# Sheet3.net
KiCad netlist of a schematic drawn in Altium Designer
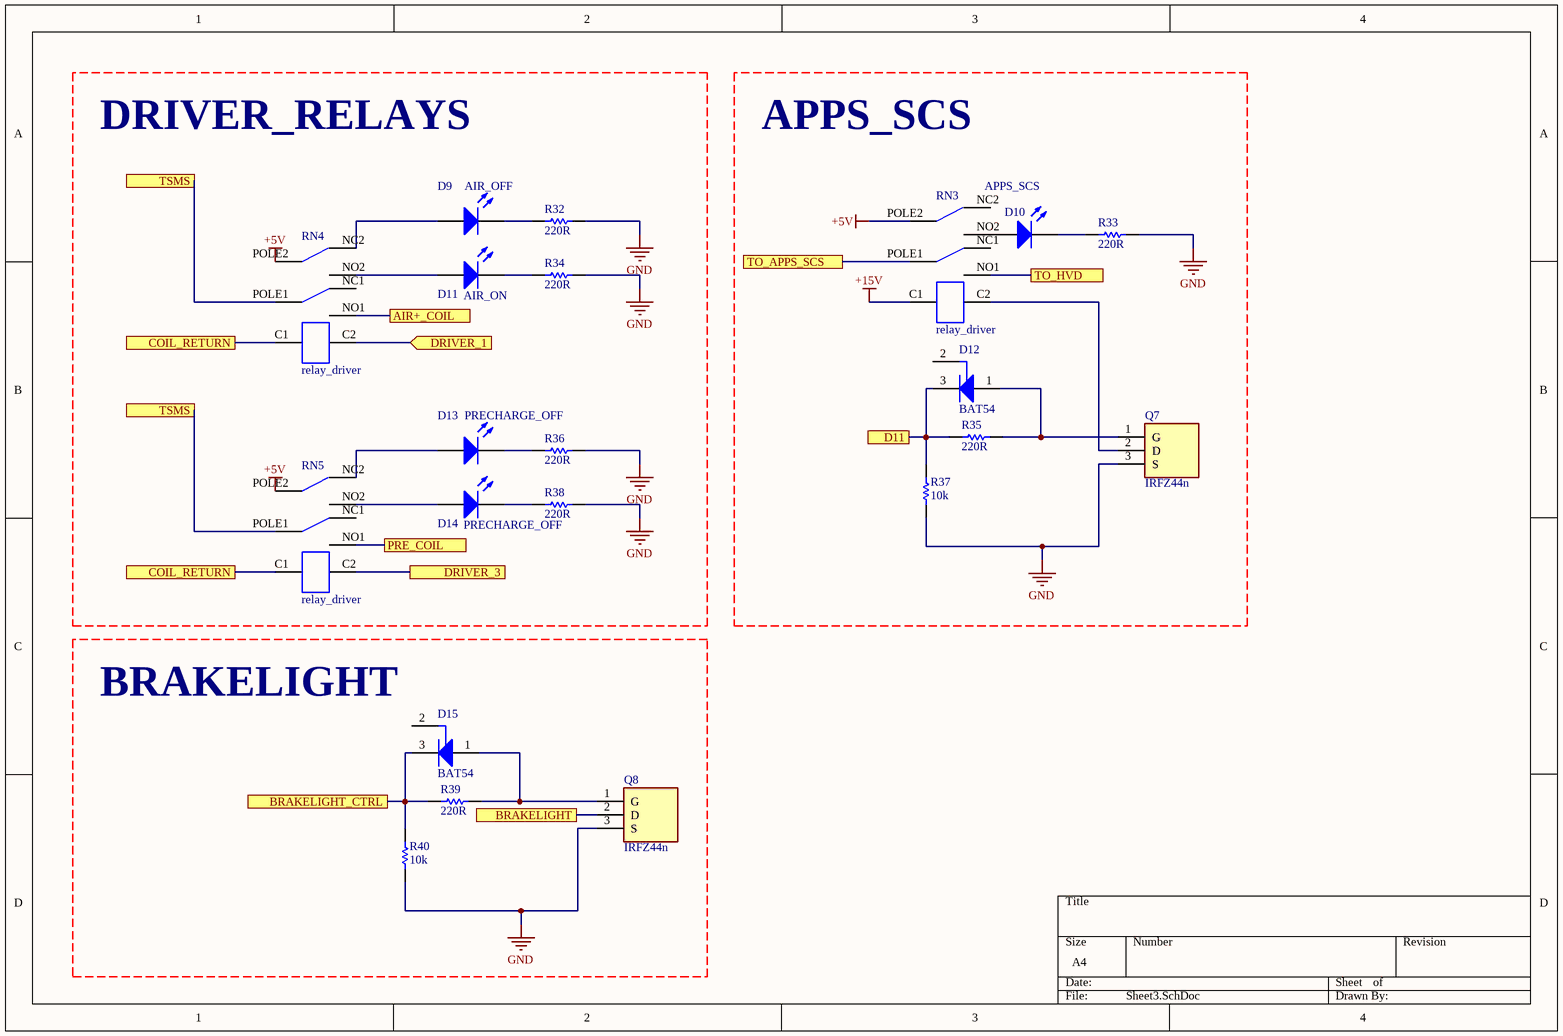
[diagram p0: Sheet3.SchDoc]

(export (version "E")
  (design (tool "Eeschema 10.0.6"))
  (components
    (comp (ref "D9")
      (value "AIR_OFF")
      (footprint "3.2X1.6X1.1")
      (description "Typical RED, GREEN, YELLOW, AMBER GaAs LED")
      (fields (field (name "PUBLISHER") "Altium Limited"))
      (libsource (lib "Miscellaneous Devices") (part "LED2"))
    )
    (comp (ref "D10")
      (value "APPS_SCS")
      (footprint "3.2X1.6X1.1")
      (description "Typical RED, GREEN, YELLOW, AMBER GaAs LED")
      (fields (field (name "PUBLISHER") "Altium Limited"))
      (libsource (lib "Miscellaneous Devices") (part "LED2"))
    )
    (comp (ref "D11")
      (value "AIR_ON")
      (footprint "3.2X1.6X1.1")
      (description "Typical RED, GREEN, YELLOW, AMBER GaAs LED")
      (fields (field (name "PUBLISHER") "Altium Limited"))
      (libsource (lib "Miscellaneous Devices") (part "LED2"))
    )
    (comp (ref "D12")
      (value "BAT54")
      (footprint "INF-SOT23_N")
      (description "Silicon Schottky Diode, SOT23, Reel, Green")
      (fields (field (name "MANUFACTURER") "Infineon"))
      (libsource (lib "Schlib1_TSAL_LV_3.1") (part "CMP-1182-00010-1"))
    )
    (comp (ref "D13")
      (value "PRECHARGE_OFF")
      (footprint "3.2X1.6X1.1")
      (description "Typical RED, GREEN, YELLOW, AMBER GaAs LED")
      (fields (field (name "PUBLISHER") "Altium Limited"))
      (libsource (lib "Miscellaneous Devices") (part "LED2"))
    )
    (comp (ref "D14")
      (value "PRECHARGE_OFF")
      (footprint "3.2X1.6X1.1")
      (description "Typical RED, GREEN, YELLOW, AMBER GaAs LED")
      (fields (field (name "PUBLISHER") "Altium Limited"))
      (libsource (lib "Miscellaneous Devices") (part "LED2"))
    )
    (comp (ref "D15")
      (value "BAT54")
      (footprint "INF-SOT23_N")
      (description "Silicon Schottky Diode, SOT23, Reel, Green")
      (fields (field (name "MANUFACTURER") "Infineon"))
      (libsource (lib "Schlib1_TSAL_LV_3.1") (part "CMP-1182-00010-1"))
    )
    (comp (ref "Q7")
      (value "IRFZ44n")
      (footprint "SamacSys:TO254P483X1016X2223-3P")
      (description "Transistor")
      (libsource (lib "*") (part "IRFZ44n"))
    )
    (comp (ref "Q8")
      (value "IRFZ44n")
      (footprint "SamacSys:TO254P483X1016X2223-3P")
      (description "Transistor")
      (libsource (lib "*") (part "IRFZ44n"))
    )
    (comp (ref "R32")
      (value "220R")
      (footprint "R1206")
      (fields (field (name "PART NUMBER") "CRCW120647K0FKEA") (field (name "MANUFACTURER") "Vishay Dale"))
      (libsource (lib "Schlib1") (part "RES"))
    )
    (comp (ref "R33")
      (value "220R")
      (footprint "R1206")
      (fields (field (name "PART NUMBER") "CRCW120647K0FKEA") (field (name "MANUFACTURER") "Vishay Dale"))
      (libsource (lib "Schlib1") (part "RES"))
    )
    (comp (ref "R34")
      (value "220R")
      (footprint "R1206")
      (fields (field (name "PART NUMBER") "CRCW120647K0FKEA") (field (name "MANUFACTURER") "Vishay Dale"))
      (libsource (lib "Schlib1") (part "RES"))
    )
    (comp (ref "R35")
      (value "220R")
      (footprint "R1206")
      (fields (field (name "PART NUMBER") "CRCW120647K0FKEA") (field (name "MANUFACTURER") "Vishay Dale"))
      (libsource (lib "Schlib1") (part "RES"))
    )
    (comp (ref "R36")
      (value "220R")
      (footprint "R1206")
      (fields (field (name "PART NUMBER") "CRCW120647K0FKEA") (field (name "MANUFACTURER") "Vishay Dale"))
      (libsource (lib "Schlib1") (part "RES"))
    )
    (comp (ref "R37")
      (value "10k")
      (footprint "R1206")
      (fields (field (name "PART NUMBER") "CRCW120647K0FKEA") (field (name "MANUFACTURER") "Vishay Dale"))
      (libsource (lib "Schlib1") (part "RES"))
    )
    (comp (ref "R38")
      (value "220R")
      (footprint "R1206")
      (fields (field (name "PART NUMBER") "CRCW120647K0FKEA") (field (name "MANUFACTURER") "Vishay Dale"))
      (libsource (lib "Schlib1") (part "RES"))
    )
    (comp (ref "R39")
      (value "220R")
      (footprint "R1206")
      (fields (field (name "PART NUMBER") "CRCW120647K0FKEA") (field (name "MANUFACTURER") "Vishay Dale"))
      (libsource (lib "Schlib1") (part "RES"))
    )
    (comp (ref "R40")
      (value "10k")
      (footprint "R1206")
      (fields (field (name "PART NUMBER") "CRCW120647K0FKEA") (field (name "MANUFACTURER") "Vishay Dale"))
      (libsource (lib "Schlib1") (part "RES"))
    )
    (comp (ref "RN3")
      (value "relay_driver")
      (footprint "OMRON_12_RELAY")
      (libsource (lib "Schlib1") (part "relay_driver"))
    )
    (comp (ref "RN4")
      (value "relay_driver")
      (footprint "OMRON_12_RELAY")
      (libsource (lib "Schlib1") (part "relay_driver"))
    )
    (comp (ref "RN5")
      (value "relay_driver")
      (footprint "OMRON_12_RELAY")
      (libsource (lib "Schlib1") (part "relay_driver"))
    )
  )
  (nets
    (net (code "1") (name "+5V") (class "Default")
      (node (ref "RN3") (pin "POLE2") (pinfunction "POLE2_POLE2") (pintype "passive"))
      (node (ref "RN4") (pin "POLE2") (pinfunction "POLE2_POLE2") (pintype "passive"))
      (node (ref "RN5") (pin "POLE2") (pinfunction "POLE2_POLE2") (pintype "passive"))
    )
    (net (code "2") (name "+15V") (class "Default")
      (node (ref "RN3") (pin "C1") (pinfunction "C1_C1") (pintype "passive"))
    )
    (net (code "3") (name "/AIR+_COIL") (class "Default")
      (node (ref "RN4") (pin "NO1") (pinfunction "NO1_NO1") (pintype "passive"))
    )
    (net (code "4") (name "/BRAKELIGHT") (class "Default")
      (node (ref "Q8") (pin "2") (pinfunction "D_2") (pintype "passive"))
    )
    (net (code "5") (name "/BRAKELIGHT_CTRL") (class "Default")
      (node (ref "D15") (pin "3") (pinfunction "K_3") (pintype "passive"))
      (node (ref "R39") (pin "1") (pinfunction "1_1") (pintype "passive"))
      (node (ref "R40") (pin "2") (pinfunction "2_2") (pintype "passive"))
    )
    (net (code "6") (name "/COIL_RETURN") (class "Default")
      (node (ref "RN4") (pin "C1") (pinfunction "C1_C1") (pintype "passive"))
      (node (ref "RN5") (pin "C1") (pinfunction "C1_C1") (pintype "passive"))
    )
    (net (code "7") (name "/D11") (class "Default")
      (node (ref "D12") (pin "3") (pinfunction "K_3") (pintype "passive"))
      (node (ref "R35") (pin "1") (pinfunction "1_1") (pintype "passive"))
      (node (ref "R37") (pin "2") (pinfunction "2_2") (pintype "passive"))
    )
    (net (code "8") (name "/DRIVER_1") (class "Default")
      (node (ref "RN4") (pin "C2") (pinfunction "C2_C2") (pintype "passive"))
    )
    (net (code "9") (name "/DRIVER_3") (class "Default")
      (node (ref "RN5") (pin "C2") (pinfunction "C2_C2") (pintype "passive"))
    )
    (net (code "10") (name "/PRE_COIL") (class "Default")
      (node (ref "RN5") (pin "NO1") (pinfunction "NO1_NO1") (pintype "passive"))
    )
    (net (code "11") (name "/TO_APPS_SCS") (class "Default")
      (node (ref "RN3") (pin "POLE1") (pinfunction "POLE1_POLE1") (pintype "passive"))
    )
    (net (code "12") (name "/TO_HVD") (class "Default")
      (node (ref "RN3") (pin "NO1") (pinfunction "NO1_NO1") (pintype "passive"))
    )
    (net (code "13") (name "/TSMS") (class "Default")
      (node (ref "RN4") (pin "POLE1") (pinfunction "POLE1_POLE1") (pintype "passive"))
      (node (ref "RN5") (pin "POLE1") (pinfunction "POLE1_POLE1") (pintype "passive"))
    )
    (net (code "14") (name "GND") (class "Default")
      (node (ref "Q7") (pin "3") (pinfunction "S_3") (pintype "passive"))
      (node (ref "Q8") (pin "3") (pinfunction "S_3") (pintype "passive"))
      (node (ref "R32") (pin "2") (pinfunction "2_2") (pintype "passive"))
      (node (ref "R33") (pin "2") (pinfunction "2_2") (pintype "passive"))
      (node (ref "R34") (pin "2") (pinfunction "2_2") (pintype "passive"))
      (node (ref "R36") (pin "2") (pinfunction "2_2") (pintype "passive"))
      (node (ref "R37") (pin "1") (pinfunction "1_1") (pintype "passive"))
      (node (ref "R38") (pin "2") (pinfunction "2_2") (pintype "passive"))
      (node (ref "R40") (pin "1") (pinfunction "1_1") (pintype "passive"))
    )
    (net (code "15") (name "Net-(D9-A)") (class "Default")
      (node (ref "D9") (pin "1") (pinfunction "A_1") (pintype "passive"))
      (node (ref "RN4") (pin "NC2") (pinfunction "NC2_NC2") (pintype "passive"))
    )
    (net (code "16") (name "Net-(D9-K)") (class "Default")
      (node (ref "D9") (pin "2") (pinfunction "K_2") (pintype "passive"))
      (node (ref "R32") (pin "1") (pinfunction "1_1") (pintype "passive"))
    )
    (net (code "17") (name "Net-(D10-A)") (class "Default")
      (node (ref "D10") (pin "1") (pinfunction "A_1") (pintype "passive"))
      (node (ref "RN3") (pin "NO2") (pinfunction "NO2_NO2") (pintype "passive"))
    )
    (net (code "18") (name "Net-(D10-K)") (class "Default")
      (node (ref "D10") (pin "2") (pinfunction "K_2") (pintype "passive"))
      (node (ref "R33") (pin "1") (pinfunction "1_1") (pintype "passive"))
    )
    (net (code "19") (name "Net-(D11-A)") (class "Default")
      (node (ref "D11") (pin "1") (pinfunction "A_1") (pintype "passive"))
      (node (ref "RN4") (pin "NO2") (pinfunction "NO2_NO2") (pintype "passive"))
    )
    (net (code "20") (name "Net-(D11-K)") (class "Default")
      (node (ref "D11") (pin "2") (pinfunction "K_2") (pintype "passive"))
      (node (ref "R34") (pin "1") (pinfunction "1_1") (pintype "passive"))
    )
    (net (code "21") (name "Net-(D12-A)") (class "Default")
      (node (ref "D12") (pin "1") (pinfunction "A_1") (pintype "passive"))
      (node (ref "Q7") (pin "1") (pinfunction "G_1") (pintype "passive"))
      (node (ref "R35") (pin "2") (pinfunction "2_2") (pintype "passive"))
    )
    (net (code "22") (name "Net-(D13-A)") (class "Default")
      (node (ref "D13") (pin "1") (pinfunction "A_1") (pintype "passive"))
      (node (ref "RN5") (pin "NC2") (pinfunction "NC2_NC2") (pintype "passive"))
    )
    (net (code "23") (name "Net-(D13-K)") (class "Default")
      (node (ref "D13") (pin "2") (pinfunction "K_2") (pintype "passive"))
      (node (ref "R36") (pin "1") (pinfunction "1_1") (pintype "passive"))
    )
    (net (code "24") (name "Net-(D14-A)") (class "Default")
      (node (ref "D14") (pin "1") (pinfunction "A_1") (pintype "passive"))
      (node (ref "RN5") (pin "NO2") (pinfunction "NO2_NO2") (pintype "passive"))
    )
    (net (code "25") (name "Net-(D14-K)") (class "Default")
      (node (ref "D14") (pin "2") (pinfunction "K_2") (pintype "passive"))
      (node (ref "R38") (pin "1") (pinfunction "1_1") (pintype "passive"))
    )
    (net (code "26") (name "Net-(D15-A)") (class "Default")
      (node (ref "D15") (pin "1") (pinfunction "A_1") (pintype "passive"))
      (node (ref "Q8") (pin "1") (pinfunction "G_1") (pintype "passive"))
      (node (ref "R39") (pin "2") (pinfunction "2_2") (pintype "passive"))
    )
    (net (code "27") (name "Net-(Q7-D)") (class "Default")
      (node (ref "Q7") (pin "2") (pinfunction "D_2") (pintype "passive"))
      (node (ref "RN3") (pin "C2") (pinfunction "C2_C2") (pintype "passive"))
    )
    (net (code "28") (name "unconnected-(D12-NC-Pad2)") (class "Default")
      (node (ref "D12") (pin "2") (pinfunction "NC_2") (pintype "passive"))
    )
    (net (code "29") (name "unconnected-(D15-NC-Pad2)") (class "Default")
      (node (ref "D15") (pin "2") (pinfunction "NC_2") (pintype "passive"))
    )
    (net (code "30") (name "unconnected-(RN3-PadNC1)") (class "Default")
      (node (ref "RN3") (pin "NC1") (pinfunction "NC1_NC1") (pintype "passive"))
    )
    (net (code "31") (name "unconnected-(RN3-PadNC2)") (class "Default")
      (node (ref "RN3") (pin "NC2") (pinfunction "NC2_NC2") (pintype "passive"))
    )
    (net (code "32") (name "unconnected-(RN4-PadNC1)") (class "Default")
      (node (ref "RN4") (pin "NC1") (pinfunction "NC1_NC1") (pintype "passive"))
    )
    (net (code "33") (name "unconnected-(RN5-PadNC1)") (class "Default")
      (node (ref "RN5") (pin "NC1") (pinfunction "NC1_NC1") (pintype "passive"))
    )
  )
)
